# TuringFront.net
KiCad netlist of a schematic drawn in EAGLE
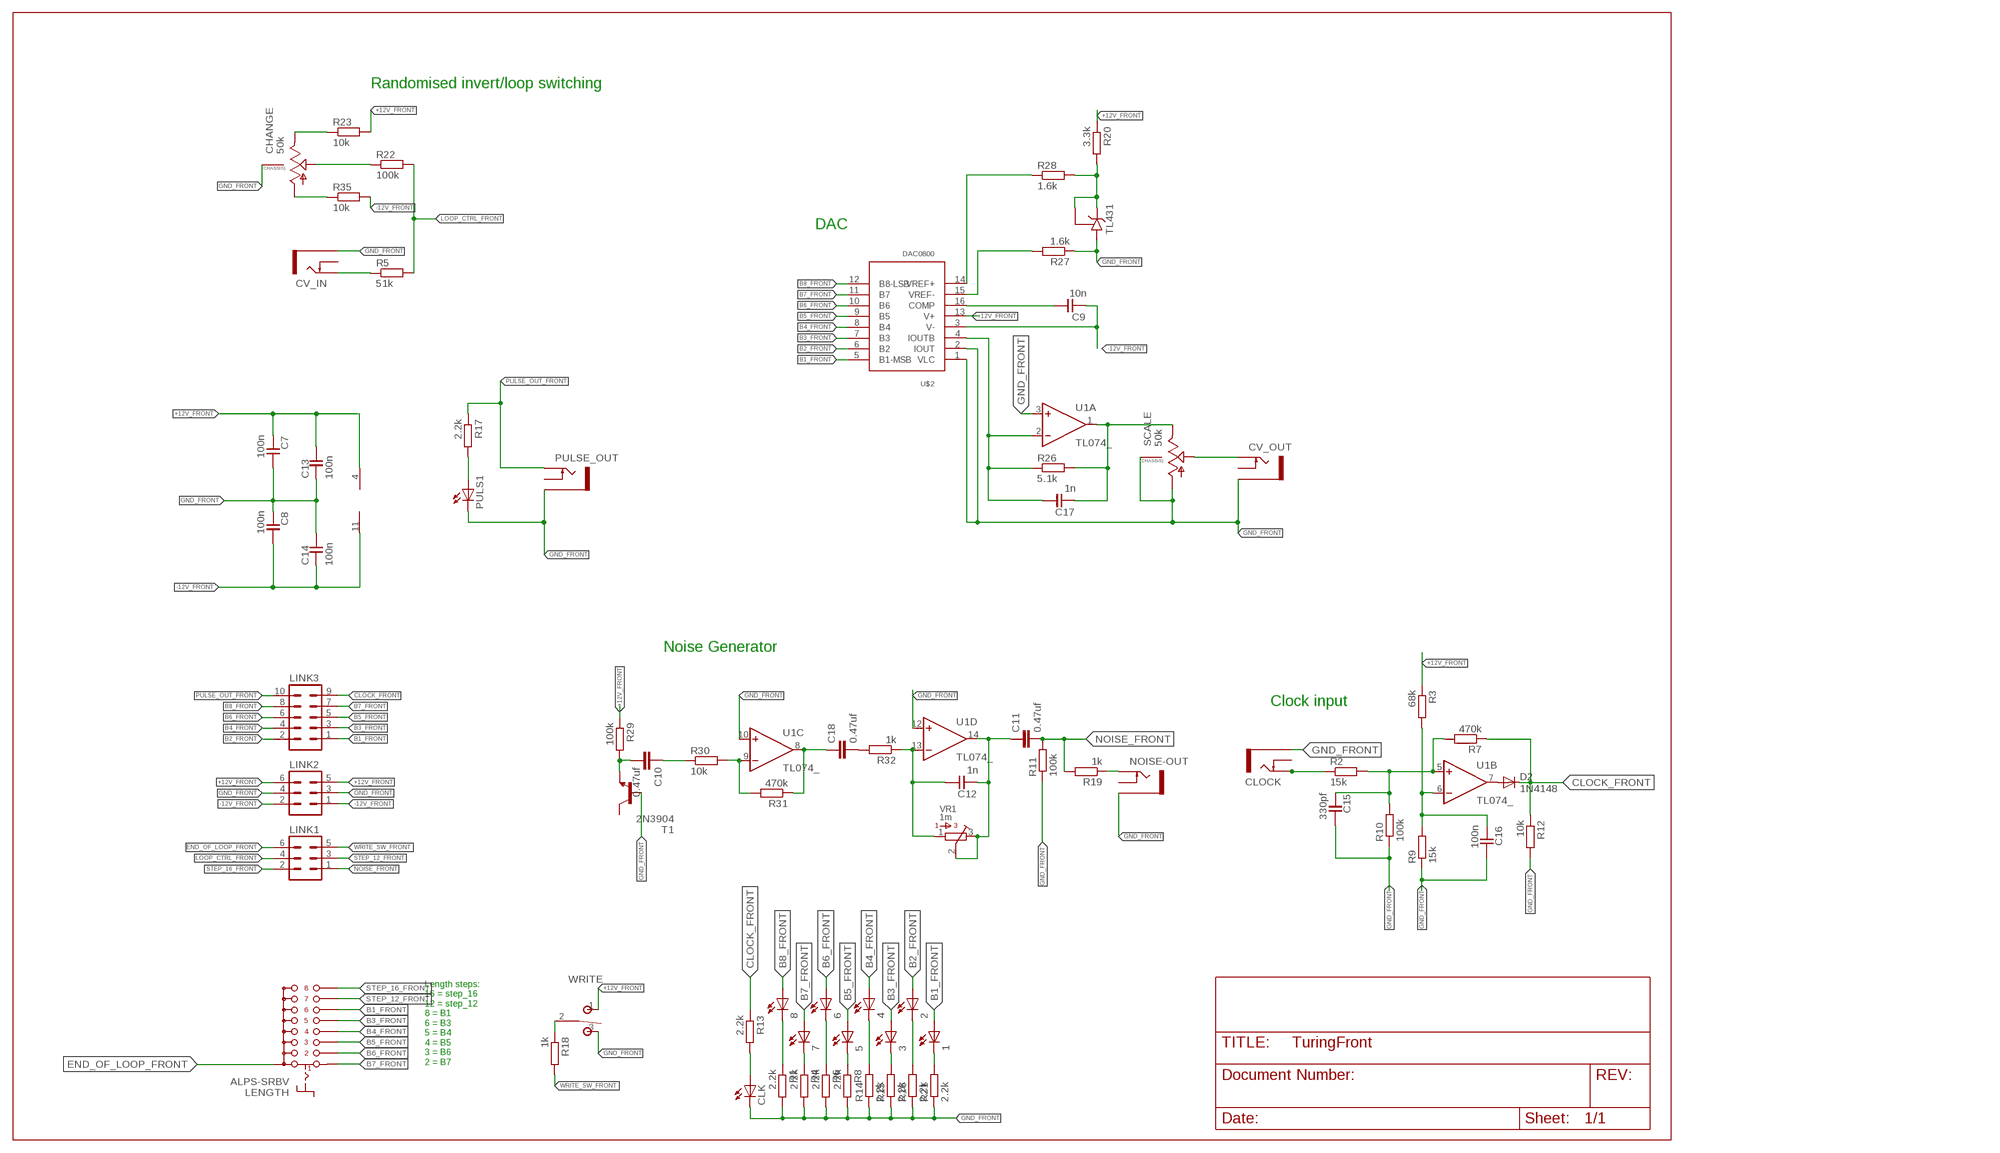
[diagram p0: schematic, sheet 1]

(export (version "E")
  (design (tool "Eeschema 10.0.6"))
  (components
    (comp (ref "1")
      (value "LED3MM")
      (footprint "eagle-import:LED3MM")
      (libsource (lib "eagle-import") (part "LED3MM"))
    )
    (comp (ref "2")
      (value "LED3MM")
      (footprint "eagle-import:LED3MM")
      (libsource (lib "eagle-import") (part "LED3MM"))
    )
    (comp (ref "3")
      (value "LED3MM")
      (footprint "eagle-import:LED3MM")
      (libsource (lib "eagle-import") (part "LED3MM"))
    )
    (comp (ref "4")
      (value "LED3MM")
      (footprint "eagle-import:LED3MM")
      (libsource (lib "eagle-import") (part "LED3MM"))
    )
    (comp (ref "5")
      (value "LED3MM")
      (footprint "eagle-import:LED3MM")
      (libsource (lib "eagle-import") (part "LED3MM"))
    )
    (comp (ref "6")
      (value "LED3MM")
      (footprint "eagle-import:LED3MM")
      (libsource (lib "eagle-import") (part "LED3MM"))
    )
    (comp (ref "7")
      (value "LED3MM")
      (footprint "eagle-import:LED3MM")
      (libsource (lib "eagle-import") (part "LED3MM"))
    )
    (comp (ref "8")
      (value "LED3MM")
      (footprint "eagle-import:LED3MM")
      (libsource (lib "eagle-import") (part "LED3MM"))
    )
    (comp (ref "C7")
      (value "100n")
      (footprint "eagle-import:C050-024X044")
      (libsource (lib "eagle-import") (part "C-EU050-024X044"))
    )
    (comp (ref "C8")
      (value "100n")
      (footprint "eagle-import:C050-024X044")
      (libsource (lib "eagle-import") (part "C-EU050-024X044"))
    )
    (comp (ref "C9")
      (value "10n")
      (footprint "eagle-import:C050-024X044")
      (libsource (lib "eagle-import") (part "C-EU050-024X044"))
    )
    (comp (ref "C10")
      (value "0.47uf")
      (footprint "eagle-import:C050-035X075")
      (libsource (lib "eagle-import") (part "rcl_C-EU050-035X075"))
    )
    (comp (ref "C11")
      (value "0.47uf")
      (footprint "eagle-import:C050-035X075")
      (libsource (lib "eagle-import") (part "rcl_C-EU050-035X075"))
    )
    (comp (ref "C12")
      (value "1n")
      (footprint "eagle-import:C050-024X044")
      (libsource (lib "eagle-import") (part "C-EU050-024X044"))
    )
    (comp (ref "C13")
      (value "100n")
      (footprint "eagle-import:C050-024X044")
      (libsource (lib "eagle-import") (part "C-EU050-024X044"))
    )
    (comp (ref "C14")
      (value "100n")
      (footprint "eagle-import:C050-024X044")
      (libsource (lib "eagle-import") (part "C-EU050-024X044"))
    )
    (comp (ref "C15")
      (value "330pf")
      (footprint "eagle-import:C050-024X044")
      (libsource (lib "eagle-import") (part "C-EU050-024X044"))
    )
    (comp (ref "C16")
      (value "100n")
      (footprint "eagle-import:C050-024X044")
      (libsource (lib "eagle-import") (part "C-EU050-024X044"))
    )
    (comp (ref "C17")
      (value "1n")
      (footprint "eagle-import:C050-024X044")
      (libsource (lib "eagle-import") (part "C-EU050-024X044"))
    )
    (comp (ref "C18")
      (value "0.47uf")
      (footprint "eagle-import:C050-035X075")
      (libsource (lib "eagle-import") (part "rcl_C-EU050-035X075"))
    )
    (comp (ref "CHANGE")
      (value "50k")
      (footprint "eagle-import:9MM_SNAP-IN_POT")
      (libsource (lib "eagle-import") (part "9MM_SNAP-IN_POT_CHASSIS"))
    )
    (comp (ref "CLK")
      (value "LED3MM")
      (footprint "eagle-import:LED3MM")
      (libsource (lib "eagle-import") (part "LED3MM"))
    )
    (comp (ref "CLOCK")
      (value "THONKICONNNEW")
      (footprint "eagle-import:WQP-PJ301M-12_JACK")
      (libsource (lib "eagle-import") (part "THONKICONNNEW"))
    )
    (comp (ref "CV_IN")
      (value "THONKICONNNEW")
      (footprint "eagle-import:WQP-PJ301M-12_JACK")
      (libsource (lib "eagle-import") (part "THONKICONNNEW"))
    )
    (comp (ref "CV_OUT")
      (value "THONKICONNNEW")
      (footprint "eagle-import:WQP-PJ301M-12_JACK")
      (libsource (lib "eagle-import") (part "THONKICONNNEW"))
    )
    (comp (ref "D2")
      (value "1N4148")
      (footprint "eagle-import:DO35-7")
      (libsource (lib "eagle-import") (part "SMALL_DIODEDO35-7"))
    )
    (comp (ref "LENGTH")
      (value "ALPS-SRBV")
      (footprint "eagle-import:ALPS-SRBV")
      (libsource (lib "eagle-import") (part "ALPS-SRBV"))
    )
    (comp (ref "LINK1")
      (value "MA03-2BACKSIDE")
      (footprint "eagle-import:MA03-2BACKSIDE")
      (libsource (lib "eagle-import") (part "MA03-2BACKSIDE"))
    )
    (comp (ref "LINK2")
      (value "MA03-2BACKSIDE")
      (footprint "eagle-import:MA03-2BACKSIDE")
      (libsource (lib "eagle-import") (part "MA03-2BACKSIDE"))
    )
    (comp (ref "LINK3")
      (value "10PIN_BACKSIDE")
      (footprint "eagle-import:10PIN_BACKSIDE")
      (libsource (lib "eagle-import") (part "10PIN_BACKSIDE"))
    )
    (comp (ref "NOISE-OUT")
      (value "THONKICONNNEW")
      (footprint "eagle-import:WQP-PJ301M-12_JACK")
      (libsource (lib "eagle-import") (part "THONKICONNNEW"))
    )
    (comp (ref "PULS1")
      (value "LED3MM")
      (footprint "eagle-import:LED3MM")
      (libsource (lib "eagle-import") (part "LED3MM"))
    )
    (comp (ref "PULSE_OUT")
      (value "THONKICONNNEW")
      (footprint "eagle-import:WQP-PJ301M-12_JACK")
      (libsource (lib "eagle-import") (part "THONKICONNNEW"))
    )
    (comp (ref "R1")
      (value "2.2k")
      (footprint "eagle-import:0207_7")
      (libsource (lib "eagle-import") (part "R-EU_0207/7"))
    )
    (comp (ref "R2")
      (value "15k")
      (footprint "eagle-import:0207_7")
      (libsource (lib "eagle-import") (part "R-EU_0207/7"))
    )
    (comp (ref "R3")
      (value "68k")
      (footprint "eagle-import:0207_7")
      (libsource (lib "eagle-import") (part "R-EU_0207/7"))
    )
    (comp (ref "R4")
      (value "2.2k")
      (footprint "eagle-import:0207_7")
      (libsource (lib "eagle-import") (part "R-EU_0207/7"))
    )
    (comp (ref "R5")
      (value "51k")
      (footprint "eagle-import:0207_7")
      (libsource (lib "eagle-import") (part "R-EU_0207/7"))
    )
    (comp (ref "R6")
      (value "2.2k")
      (footprint "eagle-import:0207_7")
      (libsource (lib "eagle-import") (part "R-EU_0207/7"))
    )
    (comp (ref "R7")
      (value "470k")
      (footprint "eagle-import:0207_7")
      (libsource (lib "eagle-import") (part "R-EU_0207/7"))
    )
    (comp (ref "R8")
      (value "2.2k")
      (footprint "eagle-import:0207_7")
      (libsource (lib "eagle-import") (part "R-EU_0207/7"))
    )
    (comp (ref "R9")
      (value "15k")
      (footprint "eagle-import:0207_7")
      (libsource (lib "eagle-import") (part "R-EU_0207/7"))
    )
    (comp (ref "R10")
      (value "100k")
      (footprint "eagle-import:0207_7")
      (libsource (lib "eagle-import") (part "R-EU_0207/7"))
    )
    (comp (ref "R11")
      (value "100k")
      (footprint "eagle-import:7MM_RESISTOR")
      (libsource (lib "eagle-import") (part "RESISTOR7MM"))
    )
    (comp (ref "R12")
      (value "10k")
      (footprint "eagle-import:0207_7")
      (libsource (lib "eagle-import") (part "R-EU_0207/7"))
    )
    (comp (ref "R13")
      (value "2.2k")
      (footprint "eagle-import:0207_7")
      (libsource (lib "eagle-import") (part "R-EU_0207/7"))
    )
    (comp (ref "R14")
      (value "2.2k")
      (footprint "eagle-import:0207_7")
      (libsource (lib "eagle-import") (part "R-EU_0207/7"))
    )
    (comp (ref "R15")
      (value "2.2k")
      (footprint "eagle-import:0207_7")
      (libsource (lib "eagle-import") (part "R-EU_0207/7"))
    )
    (comp (ref "R16")
      (value "2.2k")
      (footprint "eagle-import:0207_7")
      (libsource (lib "eagle-import") (part "R-EU_0207/7"))
    )
    (comp (ref "R17")
      (value "2.2k")
      (footprint "eagle-import:0207_7")
      (libsource (lib "eagle-import") (part "R-EU_0207/7"))
    )
    (comp (ref "R18")
      (value "1k")
      (footprint "eagle-import:0207_7")
      (libsource (lib "eagle-import") (part "R-EU_0207/7"))
    )
    (comp (ref "R19")
      (value "1k")
      (footprint "eagle-import:0207_7")
      (libsource (lib "eagle-import") (part "R-EU_0207/7"))
    )
    (comp (ref "R20")
      (value "3.3k")
      (footprint "eagle-import:0207_7")
      (libsource (lib "eagle-import") (part "R-EU_0207/7"))
    )
    (comp (ref "R21")
      (value "2.2k")
      (footprint "eagle-import:0207_7")
      (libsource (lib "eagle-import") (part "R-EU_0207/7"))
    )
    (comp (ref "R22")
      (value "100k")
      (footprint "eagle-import:0207_7")
      (libsource (lib "eagle-import") (part "R-EU_0207/7"))
    )
    (comp (ref "R23")
      (value "10k")
      (footprint "eagle-import:0207_7")
      (libsource (lib "eagle-import") (part "R-EU_0207/7"))
    )
    (comp (ref "R26")
      (value "5.1k")
      (footprint "eagle-import:0207_7")
      (libsource (lib "eagle-import") (part "R-EU_0207/7"))
    )
    (comp (ref "R27")
      (value "1.6k")
      (footprint "eagle-import:0207_7")
      (libsource (lib "eagle-import") (part "R-EU_0207/7"))
    )
    (comp (ref "R28")
      (value "1.6k")
      (footprint "eagle-import:0207_7")
      (libsource (lib "eagle-import") (part "R-EU_0207/7"))
    )
    (comp (ref "R29")
      (value "100k")
      (footprint "eagle-import:0207_7")
      (libsource (lib "eagle-import") (part "R-EU_0207/7"))
    )
    (comp (ref "R30")
      (value "10k")
      (footprint "eagle-import:0207_7")
      (libsource (lib "eagle-import") (part "R-EU_0207/7"))
    )
    (comp (ref "R31")
      (value "470k")
      (footprint "eagle-import:0207_7")
      (libsource (lib "eagle-import") (part "R-EU_0207/7"))
    )
    (comp (ref "R32")
      (value "1k")
      (footprint "eagle-import:0207_7")
      (libsource (lib "eagle-import") (part "R-EU_0207/7"))
    )
    (comp (ref "R35")
      (value "10k")
      (footprint "eagle-import:0207_7")
      (libsource (lib "eagle-import") (part "R-EU_0207/7"))
    )
    (comp (ref "SCALE")
      (value "50k")
      (footprint "eagle-import:9MM_SNAP-IN_POT")
      (libsource (lib "eagle-import") (part "9MM_SNAP-IN_POT_CHASSIS"))
    )
    (comp (ref "T1")
      (value "2N3904")
      (footprint "eagle-import:TO92")
      (libsource (lib "eagle-import") (part "2N3904"))
    )
    (comp (ref "TL431")
      (value "TL431CLP")
      (footprint "eagle-import:TO92-CLP")
      (libsource (lib "eagle-import") (part "TL431CLP"))
    )
    (comp (ref "U$2")
      (value "DAC0800")
      (footprint "eagle-import:DIL16")
      (libsource (lib "eagle-import") (part "DAC0800"))
    )
    (comp (ref "U1")
      (value "TL074_")
      (footprint "eagle-import:DIL14")
      (libsource (lib "eagle-import") (part "TL074_"))
    )
    (comp (ref "VR1")
      (value "1m")
      (footprint "eagle-import:BOURNS_3362P_TRIMMER")
      (libsource (lib "eagle-import") (part "BOURNS_3362P_TRIMMERP"))
    )
    (comp (ref "WRITE")
      (value "T-80-T-SPDT-ON-OFF-ON")
      (footprint "eagle-import:M9040P")
      (libsource (lib "eagle-import") (part "T-80-T-SPDT-ON-OFF-ON"))
    )
  )
  (nets
    (net (code "1") (name "+12V_FRONT") (class "Default")
      (node (ref "C13") (pin "1") (pinfunction "1_1") (pintype "passive"))
      (node (ref "C7") (pin "2") (pinfunction "2_2") (pintype "passive"))
      (node (ref "LINK2") (pin "5") (pinfunction "5_5") (pintype "passive"))
      (node (ref "LINK2") (pin "6") (pinfunction "6_6") (pintype "passive"))
      (node (ref "R20") (pin "1") (pinfunction "1_1") (pintype "passive"))
      (node (ref "R23") (pin "2") (pinfunction "2_2") (pintype "passive"))
      (node (ref "R29") (pin "1") (pinfunction "1_1") (pintype "passive"))
      (node (ref "R3") (pin "1") (pinfunction "1_1") (pintype "passive"))
      (node (ref "U$2") (pin "13") (pinfunction "V+_13") (pintype "bidirectional"))
      (node (ref "U1") (pin "4") (pinfunction "V+_4") (pintype "power_in"))
      (node (ref "WRITE") (pin "1") (pinfunction "O_1") (pintype "passive"))
    )
    (net (code "2") (name "-12V_FRONT") (class "Default")
      (node (ref "C14") (pin "2") (pinfunction "2_2") (pintype "passive"))
      (node (ref "C8") (pin "1") (pinfunction "1_1") (pintype "passive"))
      (node (ref "C9") (pin "2") (pinfunction "2_2") (pintype "passive"))
      (node (ref "LINK2") (pin "1") (pinfunction "1_1") (pintype "passive"))
      (node (ref "LINK2") (pin "2") (pinfunction "2_2") (pintype "passive"))
      (node (ref "R35") (pin "2") (pinfunction "2_2") (pintype "passive"))
      (node (ref "U$2") (pin "3") (pinfunction "V-_3") (pintype "bidirectional"))
      (node (ref "U1") (pin "11") (pinfunction "V-_11") (pintype "power_in"))
    )
    (net (code "3") (name "B1_FRONT") (class "Default")
      (node (ref "1") (pin "A") (pinfunction "A_A") (pintype "passive"))
      (node (ref "LENGTH") (pin "F") (pinfunction "6_F") (pintype "passive"))
      (node (ref "LINK3") (pin "1") (pinfunction "1_1") (pintype "passive"))
      (node (ref "U$2") (pin "5") (pinfunction "B1-MSB_5") (pintype "bidirectional"))
    )
    (net (code "4") (name "B2_FRONT") (class "Default")
      (node (ref "2") (pin "A") (pinfunction "A_A") (pintype "passive"))
      (node (ref "LINK3") (pin "2") (pinfunction "2_2") (pintype "passive"))
      (node (ref "U$2") (pin "6") (pinfunction "B2_6") (pintype "bidirectional"))
    )
    (net (code "5") (name "B3_FRONT") (class "Default")
      (node (ref "3") (pin "A") (pinfunction "A_A") (pintype "passive"))
      (node (ref "LENGTH") (pin "E") (pinfunction "5_E") (pintype "passive"))
      (node (ref "LINK3") (pin "3") (pinfunction "3_3") (pintype "passive"))
      (node (ref "U$2") (pin "7") (pinfunction "B3_7") (pintype "bidirectional"))
    )
    (net (code "6") (name "B4_FRONT") (class "Default")
      (node (ref "4") (pin "A") (pinfunction "A_A") (pintype "passive"))
      (node (ref "LENGTH") (pin "D") (pinfunction "4_D") (pintype "passive"))
      (node (ref "LINK3") (pin "4") (pinfunction "4_4") (pintype "passive"))
      (node (ref "U$2") (pin "8") (pinfunction "B4_8") (pintype "bidirectional"))
    )
    (net (code "7") (name "B5_FRONT") (class "Default")
      (node (ref "5") (pin "A") (pinfunction "A_A") (pintype "passive"))
      (node (ref "LENGTH") (pin "C") (pinfunction "3_C") (pintype "passive"))
      (node (ref "LINK3") (pin "5") (pinfunction "5_5") (pintype "passive"))
      (node (ref "U$2") (pin "9") (pinfunction "B5_9") (pintype "bidirectional"))
    )
    (net (code "8") (name "B6_FRONT") (class "Default")
      (node (ref "6") (pin "A") (pinfunction "A_A") (pintype "passive"))
      (node (ref "LENGTH") (pin "B") (pinfunction "2_B") (pintype "passive"))
      (node (ref "LINK3") (pin "6") (pinfunction "6_6") (pintype "passive"))
      (node (ref "U$2") (pin "10") (pinfunction "B6_10") (pintype "bidirectional"))
    )
    (net (code "9") (name "B7_FRONT") (class "Default")
      (node (ref "7") (pin "A") (pinfunction "A_A") (pintype "passive"))
      (node (ref "LENGTH") (pin "A") (pinfunction "1_A") (pintype "passive"))
      (node (ref "LINK3") (pin "7") (pinfunction "7_7") (pintype "passive"))
      (node (ref "U$2") (pin "11") (pinfunction "B7_11") (pintype "bidirectional"))
    )
    (net (code "10") (name "B8_FRONT") (class "Default")
      (node (ref "8") (pin "A") (pinfunction "A_A") (pintype "passive"))
      (node (ref "LINK3") (pin "8") (pinfunction "8_8") (pintype "passive"))
      (node (ref "U$2") (pin "12") (pinfunction "B8-LSB_12") (pintype "bidirectional"))
    )
    (net (code "11") (name "CLOCK_FRONT") (class "Default")
      (node (ref "D2") (pin "C") (pinfunction "C_C") (pintype "passive"))
      (node (ref "LINK3") (pin "9") (pinfunction "9_9") (pintype "passive"))
      (node (ref "R12") (pin "1") (pinfunction "1_1") (pintype "passive"))
      (node (ref "R13") (pin "1") (pinfunction "1_1") (pintype "passive"))
      (node (ref "R7") (pin "1") (pinfunction "1_1") (pintype "passive"))
    )
    (net (code "12") (name "END_OF_LOOP_FRONT") (class "Default")
      (node (ref "LENGTH") (pin "COM") (pinfunction "A_COM") (pintype "passive"))
      (node (ref "LENGTH") (pin "COM2") (pinfunction "A_COM2") (pintype "passive"))
      (node (ref "LINK1") (pin "6") (pinfunction "6_6") (pintype "passive"))
    )
    (net (code "13") (name "GND_FRONT") (class "Default")
      (node (ref "C13") (pin "2") (pinfunction "2_2") (pintype "passive"))
      (node (ref "C14") (pin "1") (pinfunction "1_1") (pintype "passive"))
      (node (ref "C15") (pin "1") (pinfunction "1_1") (pintype "passive"))
      (node (ref "C16") (pin "1") (pinfunction "1_1") (pintype "passive"))
      (node (ref "C7") (pin "1") (pinfunction "1_1") (pintype "passive"))
      (node (ref "C8") (pin "2") (pinfunction "2_2") (pintype "passive"))
      (node (ref "CHANGE") (pin "CHASSIS2") (pinfunction "P$1_CHASSIS2") (pintype "passive"))
      (node (ref "CLK") (pin "K") (pinfunction "C_K") (pintype "passive"))
      (node (ref "CLOCK") (pin "P$3_SLEEVE") (pinfunction "SLEEVE_P$3_SLEEVE") (pintype "passive"))
      (node (ref "CV_IN") (pin "P$3_SLEEVE") (pinfunction "SLEEVE_P$3_SLEEVE") (pintype "passive"))
      (node (ref "CV_OUT") (pin "P$3_SLEEVE") (pinfunction "SLEEVE_P$3_SLEEVE") (pintype "passive"))
      (node (ref "LINK2") (pin "3") (pinfunction "3_3") (pintype "passive"))
      (node (ref "LINK2") (pin "4") (pinfunction "4_4") (pintype "passive"))
      (node (ref "NOISE-OUT") (pin "P$3_SLEEVE") (pinfunction "SLEEVE_P$3_SLEEVE") (pintype "passive"))
      (node (ref "PULS1") (pin "K") (pinfunction "C_K") (pintype "passive"))
      (node (ref "PULSE_OUT") (pin "P$3_SLEEVE") (pinfunction "SLEEVE_P$3_SLEEVE") (pintype "passive"))
      (node (ref "R1") (pin "2") (pinfunction "2_2") (pintype "passive"))
      (node (ref "R10") (pin "1") (pinfunction "1_1") (pintype "passive"))
      (node (ref "R11") (pin "1") (pinfunction "1_1") (pintype "passive"))
      (node (ref "R12") (pin "2") (pinfunction "2_2") (pintype "passive"))
      (node (ref "R14") (pin "1") (pinfunction "1_1") (pintype "passive"))
      (node (ref "R15") (pin "1") (pinfunction "1_1") (pintype "passive"))
      (node (ref "R16") (pin "1") (pinfunction "1_1") (pintype "passive"))
      (node (ref "R21") (pin "1") (pinfunction "1_1") (pintype "passive"))
      (node (ref "R27") (pin "1") (pinfunction "1_1") (pintype "passive"))
      (node (ref "R4") (pin "2") (pinfunction "2_2") (pintype "passive"))
      (node (ref "R6") (pin "2") (pinfunction "2_2") (pintype "passive"))
      (node (ref "R8") (pin "2") (pinfunction "2_2") (pintype "passive"))
      (node (ref "R9") (pin "1") (pinfunction "1_1") (pintype "passive"))
      (node (ref "SCALE") (pin "1") (pinfunction "A_1") (pintype "passive"))
      (node (ref "SCALE") (pin "CHASSIS2") (pinfunction "P$1_CHASSIS2") (pintype "passive"))
      (node (ref "T1") (pin "2") (pinfunction "B_2") (pintype "passive"))
      (node (ref "TL431") (pin "A") (pinfunction "A_A") (pintype "passive"))
      (node (ref "U$2") (pin "1") (pinfunction "VLC_1") (pintype "bidirectional"))
      (node (ref "U$2") (pin "2") (pinfunction "IOUT_2") (pintype "bidirectional"))
      (node (ref "U1") (pin "10") (pinfunction "+IN_10") (pintype "input"))
      (node (ref "U1") (pin "12") (pinfunction "+IN_12") (pintype "input"))
      (node (ref "U1") (pin "3") (pinfunction "+IN_3") (pintype "input"))
      (node (ref "WRITE") (pin "3") (pinfunction "S_3") (pintype "passive"))
    )
    (net (code "14") (name "LOOP_CTRL_FRONT") (class "Default")
      (node (ref "LINK1") (pin "4") (pinfunction "4_4") (pintype "passive"))
      (node (ref "R22") (pin "2") (pinfunction "2_2") (pintype "passive"))
      (node (ref "R5") (pin "2") (pinfunction "2_2") (pintype "passive"))
    )
    (net (code "15") (name "NOISE_FRONT") (class "Default")
      (node (ref "C11") (pin "2") (pinfunction "2_2") (pintype "passive"))
      (node (ref "LINK1") (pin "1") (pinfunction "1_1") (pintype "passive"))
      (node (ref "R11") (pin "2") (pinfunction "2_2") (pintype "passive"))
      (node (ref "R19") (pin "2") (pinfunction "2_2") (pintype "passive"))
    )
    (net (code "16") (name "Net-(1-C)") (class "Default")
      (node (ref "1") (pin "K") (pinfunction "C_K") (pintype "passive"))
      (node (ref "R21") (pin "2") (pinfunction "2_2") (pintype "passive"))
    )
    (net (code "17") (name "Net-(2-C)") (class "Default")
      (node (ref "2") (pin "K") (pinfunction "C_K") (pintype "passive"))
      (node (ref "R16") (pin "2") (pinfunction "2_2") (pintype "passive"))
    )
    (net (code "18") (name "Net-(3-C)") (class "Default")
      (node (ref "3") (pin "K") (pinfunction "C_K") (pintype "passive"))
      (node (ref "R15") (pin "2") (pinfunction "2_2") (pintype "passive"))
    )
    (net (code "19") (name "Net-(4-C)") (class "Default")
      (node (ref "4") (pin "K") (pinfunction "C_K") (pintype "passive"))
      (node (ref "R14") (pin "2") (pinfunction "2_2") (pintype "passive"))
    )
    (net (code "20") (name "Net-(5-C)") (class "Default")
      (node (ref "5") (pin "K") (pinfunction "C_K") (pintype "passive"))
      (node (ref "R8") (pin "1") (pinfunction "1_1") (pintype "passive"))
    )
    (net (code "21") (name "Net-(6-C)") (class "Default")
      (node (ref "6") (pin "K") (pinfunction "C_K") (pintype "passive"))
      (node (ref "R6") (pin "1") (pinfunction "1_1") (pintype "passive"))
    )
    (net (code "22") (name "Net-(7-C)") (class "Default")
      (node (ref "7") (pin "K") (pinfunction "C_K") (pintype "passive"))
      (node (ref "R4") (pin "1") (pinfunction "1_1") (pintype "passive"))
    )
    (net (code "23") (name "Net-(8-C)") (class "Default")
      (node (ref "8") (pin "K") (pinfunction "C_K") (pintype "passive"))
      (node (ref "R1") (pin "1") (pinfunction "1_1") (pintype "passive"))
    )
    (net (code "24") (name "Net-(C10-Pad1)") (class "Default")
      (node (ref "C10") (pin "1") (pinfunction "1_1") (pintype "passive"))
      (node (ref "R30") (pin "1") (pinfunction "1_1") (pintype "passive"))
    )
    (net (code "25") (name "Net-(C18-Pad2)") (class "Default")
      (node (ref "C18") (pin "2") (pinfunction "2_2") (pintype "passive"))
      (node (ref "R32") (pin "2") (pinfunction "2_2") (pintype "passive"))
    )
    (net (code "26") (name "Net-(CHANGE-A)") (class "Default")
      (node (ref "CHANGE") (pin "1") (pinfunction "A_1") (pintype "passive"))
      (node (ref "R35") (pin "1") (pinfunction "1_1") (pintype "passive"))
    )
    (net (code "27") (name "Net-(CHANGE-E)") (class "Default")
      (node (ref "CHANGE") (pin "3") (pinfunction "E_3") (pintype "passive"))
      (node (ref "R23") (pin "1") (pinfunction "1_1") (pintype "passive"))
    )
    (net (code "28") (name "Net-(CHANGE-S)") (class "Default")
      (node (ref "CHANGE") (pin "2") (pinfunction "S_2") (pintype "passive"))
      (node (ref "R22") (pin "1") (pinfunction "1_1") (pintype "passive"))
    )
    (net (code "29") (name "Net-(CLK-PadA)") (class "Default")
      (node (ref "CLK") (pin "A") (pinfunction "A_A") (pintype "passive"))
      (node (ref "R13") (pin "2") (pinfunction "2_2") (pintype "passive"))
    )
    (net (code "30") (name "Net-(CLOCK-TIP)") (class "Default")
      (node (ref "CLOCK") (pin "P$1_TIP") (pinfunction "TIP_P$1_TIP") (pintype "passive"))
      (node (ref "R2") (pin "1") (pinfunction "1_1") (pintype "passive"))
    )
    (net (code "31") (name "Net-(CV_IN-TIP)") (class "Default")
      (node (ref "CV_IN") (pin "P$1_TIP") (pinfunction "TIP_P$1_TIP") (pintype "passive"))
      (node (ref "R5") (pin "1") (pinfunction "1_1") (pintype "passive"))
    )
    (net (code "32") (name "Net-(CV_OUT-TIP)") (class "Default")
      (node (ref "CV_OUT") (pin "P$1_TIP") (pinfunction "TIP_P$1_TIP") (pintype "passive"))
      (node (ref "SCALE") (pin "2") (pinfunction "S_2") (pintype "passive"))
    )
    (net (code "33") (name "Net-(NOISE-OUT-TIP)") (class "Default")
      (node (ref "NOISE-OUT") (pin "P$1_TIP") (pinfunction "TIP_P$1_TIP") (pintype "passive"))
      (node (ref "R19") (pin "1") (pinfunction "1_1") (pintype "passive"))
    )
    (net (code "34") (name "Net-(PULS1-PadA)") (class "Default")
      (node (ref "PULS1") (pin "A") (pinfunction "A_A") (pintype "passive"))
      (node (ref "R17") (pin "2") (pinfunction "2_2") (pintype "passive"))
    )
    (net (code "35") (name "Net-(R20-Pad2)") (class "Default")
      (node (ref "R20") (pin "2") (pinfunction "2_2") (pintype "passive"))
      (node (ref "R28") (pin "2") (pinfunction "2_2") (pintype "passive"))
      (node (ref "TL431") (pin "C") (pinfunction "C_C") (pintype "passive"))
      (node (ref "TL431") (pin "R") (pinfunction "R_R") (pintype "passive"))
    )
    (net (code "36") (name "Net-(SCALE-E)") (class "Default")
      (node (ref "C17") (pin "2") (pinfunction "2_2") (pintype "passive"))
      (node (ref "R26") (pin "2") (pinfunction "2_2") (pintype "passive"))
      (node (ref "SCALE") (pin "3") (pinfunction "E_3") (pintype "passive"))
      (node (ref "U1") (pin "1") (pinfunction "OUT_1") (pintype "output"))
    )
    (net (code "37") (name "Net-(T1-E)") (class "Default")
      (node (ref "C10") (pin "2") (pinfunction "2_2") (pintype "passive"))
      (node (ref "R29") (pin "2") (pinfunction "2_2") (pintype "passive"))
      (node (ref "T1") (pin "3") (pinfunction "E_3") (pintype "passive"))
    )
    (net (code "38") (name "Net-(U$2-COMP)") (class "Default")
      (node (ref "C9") (pin "1") (pinfunction "1_1") (pintype "passive"))
      (node (ref "U$2") (pin "16") (pinfunction "COMP_16") (pintype "bidirectional"))
    )
    (net (code "39") (name "Net-(U$2-IOUTB)") (class "Default")
      (node (ref "C17") (pin "1") (pinfunction "1_1") (pintype "passive"))
      (node (ref "R26") (pin "1") (pinfunction "1_1") (pintype "passive"))
      (node (ref "U$2") (pin "4") (pinfunction "IOUTB_4") (pintype "bidirectional"))
      (node (ref "U1") (pin "2") (pinfunction "-IN_2") (pintype "input"))
    )
    (net (code "40") (name "Net-(U$2-VREF+)") (class "Default")
      (node (ref "R28") (pin "1") (pinfunction "1_1") (pintype "passive"))
      (node (ref "U$2") (pin "14") (pinfunction "VREF+_14") (pintype "bidirectional"))
    )
    (net (code "41") (name "Net-(U$2-VREF-)") (class "Default")
      (node (ref "R27") (pin "2") (pinfunction "2_2") (pintype "passive"))
      (node (ref "U$2") (pin "15") (pinfunction "VREF-_15") (pintype "bidirectional"))
    )
    (net (code "42") (name "Net-(U1B-+IN)") (class "Default")
      (node (ref "C15") (pin "2") (pinfunction "2_2") (pintype "passive"))
      (node (ref "R10") (pin "2") (pinfunction "2_2") (pintype "passive"))
      (node (ref "R2") (pin "2") (pinfunction "2_2") (pintype "passive"))
      (node (ref "R7") (pin "2") (pinfunction "2_2") (pintype "passive"))
      (node (ref "U1") (pin "5") (pinfunction "+IN_5") (pintype "input"))
    )
    (net (code "43") (name "Net-(U1B--IN)") (class "Default")
      (node (ref "C16") (pin "2") (pinfunction "2_2") (pintype "passive"))
      (node (ref "R3") (pin "2") (pinfunction "2_2") (pintype "passive"))
      (node (ref "R9") (pin "2") (pinfunction "2_2") (pintype "passive"))
      (node (ref "U1") (pin "6") (pinfunction "-IN_6") (pintype "input"))
    )
    (net (code "44") (name "Net-(U1B-OUT)") (class "Default")
      (node (ref "D2") (pin "A") (pinfunction "A_A") (pintype "passive"))
      (node (ref "U1") (pin "7") (pinfunction "OUT_7") (pintype "output"))
    )
    (net (code "45") (name "Net-(U1C--IN)") (class "Default")
      (node (ref "R30") (pin "2") (pinfunction "2_2") (pintype "passive"))
      (node (ref "R31") (pin "2") (pinfunction "2_2") (pintype "passive"))
      (node (ref "U1") (pin "9") (pinfunction "-IN_9") (pintype "input"))
    )
    (net (code "46") (name "Net-(U1C-OUT)") (class "Default")
      (node (ref "C18") (pin "1") (pinfunction "1_1") (pintype "passive"))
      (node (ref "R31") (pin "1") (pinfunction "1_1") (pintype "passive"))
      (node (ref "U1") (pin "8") (pinfunction "OUT_8") (pintype "output"))
    )
    (net (code "47") (name "Net-(U1D--IN)") (class "Default")
      (node (ref "C12") (pin "1") (pinfunction "1_1") (pintype "passive"))
      (node (ref "R32") (pin "1") (pinfunction "1_1") (pintype "passive"))
      (node (ref "U1") (pin "13") (pinfunction "-IN_13") (pintype "input"))
      (node (ref "VR1") (pin "1") (pinfunction "1_1") (pintype "passive"))
    )
    (net (code "48") (name "Net-(U1D-OUT)") (class "Default")
      (node (ref "C11") (pin "1") (pinfunction "1_1") (pintype "passive"))
      (node (ref "C12") (pin "2") (pinfunction "2_2") (pintype "passive"))
      (node (ref "U1") (pin "14") (pinfunction "OUT_14") (pintype "output"))
      (node (ref "VR1") (pin "2") (pinfunction "2_2") (pintype "passive"))
      (node (ref "VR1") (pin "3") (pinfunction "3_3") (pintype "passive"))
    )
    (net (code "49") (name "Net-(WRITE-P)") (class "Default")
      (node (ref "R18") (pin "1") (pinfunction "1_1") (pintype "passive"))
      (node (ref "WRITE") (pin "2") (pinfunction "P_2") (pintype "passive"))
    )
    (net (code "50") (name "PULSE_OUT_FRONT") (class "Default")
      (node (ref "LINK3") (pin "10") (pinfunction "10_10") (pintype "passive"))
      (node (ref "PULSE_OUT") (pin "P$1_TIP") (pinfunction "TIP_P$1_TIP") (pintype "passive"))
      (node (ref "R17") (pin "1") (pinfunction "1_1") (pintype "passive"))
    )
    (net (code "51") (name "STEP_12_FRONT") (class "Default")
      (node (ref "LENGTH") (pin "G") (pinfunction "7_G") (pintype "passive"))
      (node (ref "LINK1") (pin "3") (pinfunction "3_3") (pintype "passive"))
    )
    (net (code "52") (name "STEP_16_FRONT") (class "Default")
      (node (ref "LENGTH") (pin "H") (pinfunction "8_H") (pintype "passive"))
      (node (ref "LINK1") (pin "2") (pinfunction "2_2") (pintype "passive"))
    )
    (net (code "53") (name "WRITE_SW_FRONT") (class "Default")
      (node (ref "LINK1") (pin "5") (pinfunction "5_5") (pintype "passive"))
      (node (ref "R18") (pin "2") (pinfunction "2_2") (pintype "passive"))
    )
    (net (code "54") (name "unconnected-(CLOCK-SWITCH-PadP$2_SWITCH)") (class "Default")
      (node (ref "CLOCK") (pin "P$2_SWITCH") (pinfunction "SWITCH_P$2_SWITCH") (pintype "passive"))
    )
    (net (code "55") (name "unconnected-(CV_IN-SWITCH-PadP$2_SWITCH)") (class "Default")
      (node (ref "CV_IN") (pin "P$2_SWITCH") (pinfunction "SWITCH_P$2_SWITCH") (pintype "passive"))
    )
    (net (code "56") (name "unconnected-(CV_OUT-SWITCH-PadP$2_SWITCH)") (class "Default")
      (node (ref "CV_OUT") (pin "P$2_SWITCH") (pinfunction "SWITCH_P$2_SWITCH") (pintype "passive"))
    )
    (net (code "57") (name "unconnected-(NOISE-OUT-SWITCH-PadP$2_SWITCH)") (class "Default")
      (node (ref "NOISE-OUT") (pin "P$2_SWITCH") (pinfunction "SWITCH_P$2_SWITCH") (pintype "passive"))
    )
    (net (code "58") (name "unconnected-(PULSE_OUT-SWITCH-PadP$2_SWITCH)") (class "Default")
      (node (ref "PULSE_OUT") (pin "P$2_SWITCH") (pinfunction "SWITCH_P$2_SWITCH") (pintype "passive"))
    )
    (net (code "59") (name "unconnected-(T1-C-Pad1)") (class "Default")
      (node (ref "T1") (pin "1") (pinfunction "C_1") (pintype "passive"))
    )
  )
)
